# ADC.net
KiCad netlist of a schematic drawn in Altium Designer
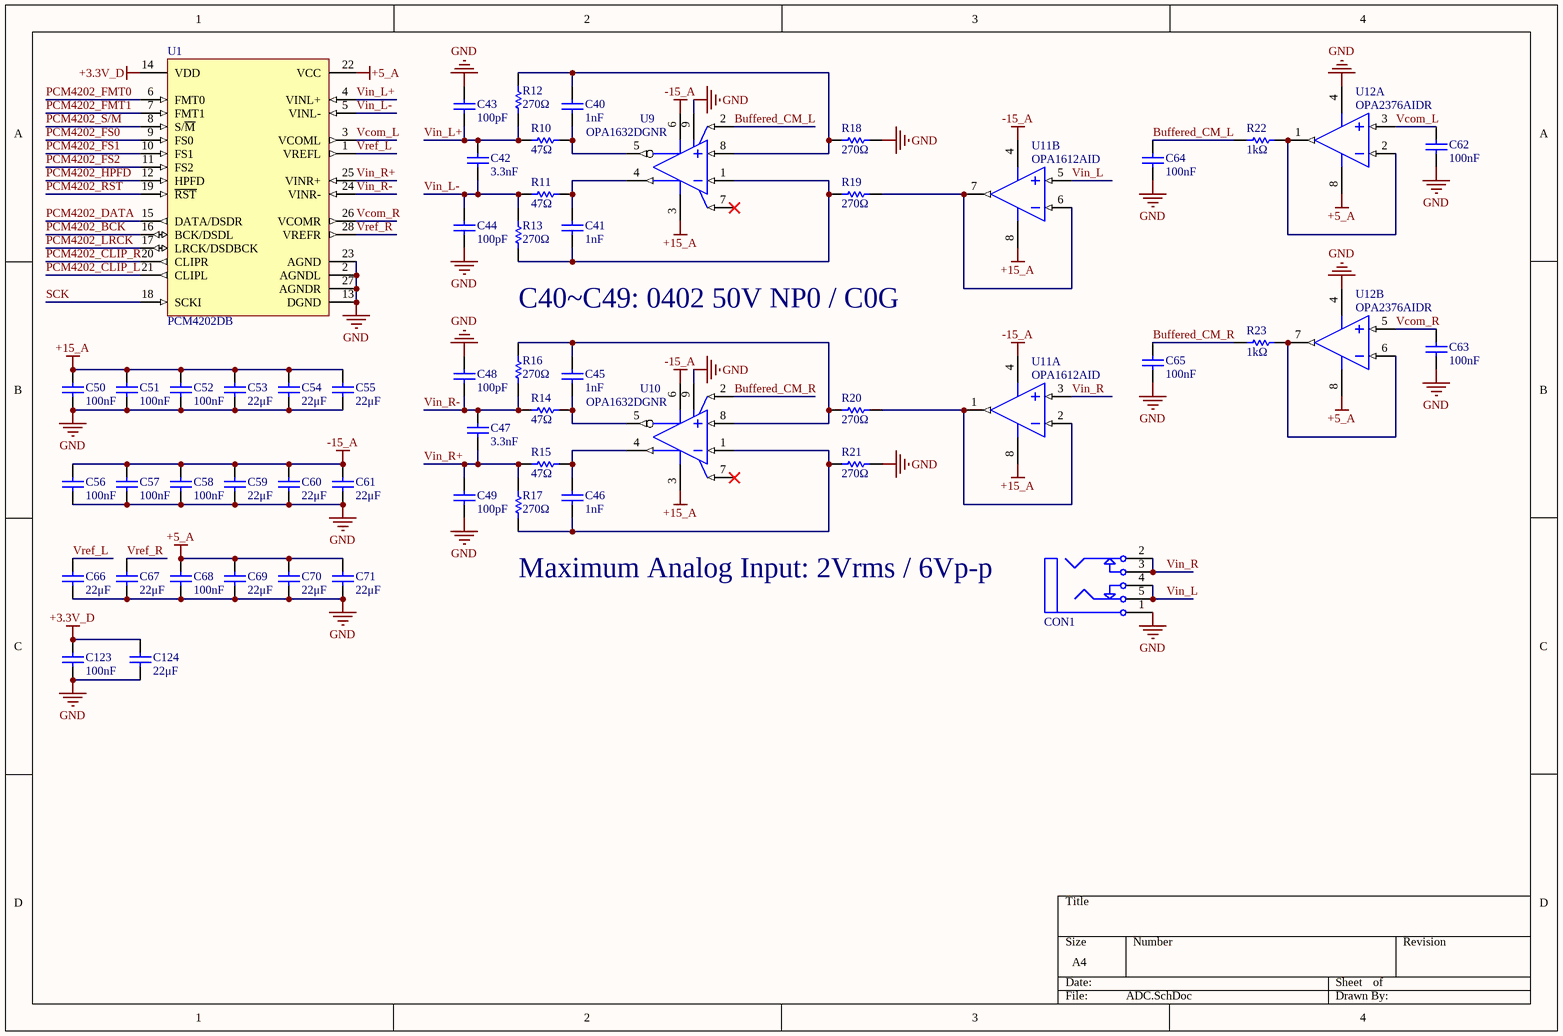
[diagram p0: ADC.SchDoc]

(export (version "E")
  (design (tool "Eeschema 10.0.6"))
  (components
    (comp (ref "C40")
      (value "1nF")
      (footprint "C 0402_L")
      (description "Capacitor")
      (fields (field (name "PUBLISHER") "Altium Limited"))
      (libsource (lib "Miscellaneous Devices") (part "Cap"))
    )
    (comp (ref "C41")
      (value "1nF")
      (footprint "C 0402_L")
      (description "Capacitor")
      (fields (field (name "PUBLISHER") "Altium Limited"))
      (libsource (lib "Miscellaneous Devices") (part "Cap"))
    )
    (comp (ref "C42")
      (value "3.3nF")
      (footprint "C 0402_L")
      (description "Capacitor")
      (fields (field (name "PUBLISHER") "Altium Limited"))
      (libsource (lib "Miscellaneous Devices") (part "Cap"))
    )
    (comp (ref "C43")
      (value "100pF")
      (footprint "C 0402_L")
      (description "Capacitor")
      (fields (field (name "PUBLISHER") "Altium Limited"))
      (libsource (lib "Miscellaneous Devices") (part "Cap"))
    )
    (comp (ref "C44")
      (value "100pF")
      (footprint "C 0402_L")
      (description "Capacitor")
      (fields (field (name "PUBLISHER") "Altium Limited"))
      (libsource (lib "Miscellaneous Devices") (part "Cap"))
    )
    (comp (ref "C45")
      (value "1nF")
      (footprint "C 0402_L")
      (description "Capacitor")
      (fields (field (name "PUBLISHER") "Altium Limited"))
      (libsource (lib "Miscellaneous Devices") (part "Cap"))
    )
    (comp (ref "C46")
      (value "1nF")
      (footprint "C 0402_L")
      (description "Capacitor")
      (fields (field (name "PUBLISHER") "Altium Limited"))
      (libsource (lib "Miscellaneous Devices") (part "Cap"))
    )
    (comp (ref "C47")
      (value "3.3nF")
      (footprint "C 0402_L")
      (description "Capacitor")
      (fields (field (name "PUBLISHER") "Altium Limited"))
      (libsource (lib "Miscellaneous Devices") (part "Cap"))
    )
    (comp (ref "C48")
      (value "100pF")
      (footprint "C 0402_L")
      (description "Capacitor")
      (fields (field (name "PUBLISHER") "Altium Limited"))
      (libsource (lib "Miscellaneous Devices") (part "Cap"))
    )
    (comp (ref "C49")
      (value "100pF")
      (footprint "C 0402_L")
      (description "Capacitor")
      (fields (field (name "PUBLISHER") "Altium Limited"))
      (libsource (lib "Miscellaneous Devices") (part "Cap"))
    )
    (comp (ref "C50")
      (value "100nF")
      (footprint "C 0402_L")
      (description "Capacitor")
      (fields (field (name "PUBLISHER") "Altium Limited"))
      (libsource (lib "Miscellaneous Devices") (part "Cap"))
    )
    (comp (ref "C51")
      (value "100nF")
      (footprint "C 0402_L")
      (description "Capacitor")
      (fields (field (name "PUBLISHER") "Altium Limited"))
      (libsource (lib "Miscellaneous Devices") (part "Cap"))
    )
    (comp (ref "C52")
      (value "100nF")
      (footprint "C 0402_L")
      (description "Capacitor")
      (fields (field (name "PUBLISHER") "Altium Limited"))
      (libsource (lib "Miscellaneous Devices") (part "Cap"))
    )
    (comp (ref "C53")
      (value "22μF")
      (footprint "0805_C")
      (description "Capacitor")
      (fields (field (name "PUBLISHER") "Altium Limited"))
      (libsource (lib "Miscellaneous Devices") (part "Cap"))
    )
    (comp (ref "C54")
      (value "22μF")
      (footprint "0805_C")
      (description "Capacitor")
      (fields (field (name "PUBLISHER") "Altium Limited"))
      (libsource (lib "Miscellaneous Devices") (part "Cap"))
    )
    (comp (ref "C55")
      (value "22μF")
      (footprint "0805_C")
      (description "Capacitor")
      (fields (field (name "PUBLISHER") "Altium Limited"))
      (libsource (lib "Miscellaneous Devices") (part "Cap"))
    )
    (comp (ref "C56")
      (value "100nF")
      (footprint "C 0402_L")
      (description "Capacitor")
      (fields (field (name "PUBLISHER") "Altium Limited"))
      (libsource (lib "Miscellaneous Devices") (part "Cap"))
    )
    (comp (ref "C57")
      (value "100nF")
      (footprint "C 0402_L")
      (description "Capacitor")
      (fields (field (name "PUBLISHER") "Altium Limited"))
      (libsource (lib "Miscellaneous Devices") (part "Cap"))
    )
    (comp (ref "C58")
      (value "100nF")
      (footprint "C 0402_L")
      (description "Capacitor")
      (fields (field (name "PUBLISHER") "Altium Limited"))
      (libsource (lib "Miscellaneous Devices") (part "Cap"))
    )
    (comp (ref "C59")
      (value "22μF")
      (footprint "0805_C")
      (description "Capacitor")
      (fields (field (name "PUBLISHER") "Altium Limited"))
      (libsource (lib "Miscellaneous Devices") (part "Cap"))
    )
    (comp (ref "C60")
      (value "22μF")
      (footprint "0805_C")
      (description "Capacitor")
      (fields (field (name "PUBLISHER") "Altium Limited"))
      (libsource (lib "Miscellaneous Devices") (part "Cap"))
    )
    (comp (ref "C61")
      (value "22μF")
      (footprint "0805_C")
      (description "Capacitor")
      (fields (field (name "PUBLISHER") "Altium Limited"))
      (libsource (lib "Miscellaneous Devices") (part "Cap"))
    )
    (comp (ref "C62")
      (value "100nF")
      (footprint "C 0402_L")
      (description "Capacitor")
      (fields (field (name "PUBLISHER") "Altium Limited"))
      (libsource (lib "Miscellaneous Devices") (part "Cap"))
    )
    (comp (ref "C63")
      (value "100nF")
      (footprint "C 0402_L")
      (description "Capacitor")
      (fields (field (name "PUBLISHER") "Altium Limited"))
      (libsource (lib "Miscellaneous Devices") (part "Cap"))
    )
    (comp (ref "C64")
      (value "100nF")
      (footprint "C 0402_L")
      (description "Capacitor")
      (fields (field (name "PUBLISHER") "Altium Limited"))
      (libsource (lib "Miscellaneous Devices") (part "Cap"))
    )
    (comp (ref "C65")
      (value "100nF")
      (footprint "C 0402_L")
      (description "Capacitor")
      (fields (field (name "PUBLISHER") "Altium Limited"))
      (libsource (lib "Miscellaneous Devices") (part "Cap"))
    )
    (comp (ref "C66")
      (value "22μF")
      (footprint "0805_C")
      (description "Capacitor")
      (fields (field (name "PUBLISHER") "Altium Limited"))
      (libsource (lib "Miscellaneous Devices") (part "Cap"))
    )
    (comp (ref "C67")
      (value "22μF")
      (footprint "0805_C")
      (description "Capacitor")
      (fields (field (name "PUBLISHER") "Altium Limited"))
      (libsource (lib "Miscellaneous Devices") (part "Cap"))
    )
    (comp (ref "C68")
      (value "100nF")
      (footprint "C 0402_L")
      (description "Capacitor")
      (fields (field (name "PUBLISHER") "Altium Limited"))
      (libsource (lib "Miscellaneous Devices") (part "Cap"))
    )
    (comp (ref "C69")
      (value "22μF")
      (footprint "0805_C")
      (description "Capacitor")
      (fields (field (name "PUBLISHER") "Altium Limited"))
      (libsource (lib "Miscellaneous Devices") (part "Cap"))
    )
    (comp (ref "C70")
      (value "22μF")
      (footprint "0805_C")
      (description "Capacitor")
      (fields (field (name "PUBLISHER") "Altium Limited"))
      (libsource (lib "Miscellaneous Devices") (part "Cap"))
    )
    (comp (ref "C71")
      (value "22μF")
      (footprint "0805_C")
      (description "Capacitor")
      (fields (field (name "PUBLISHER") "Altium Limited"))
      (libsource (lib "Miscellaneous Devices") (part "Cap"))
    )
    (comp (ref "C123")
      (value "100nF")
      (footprint "C 0402_L")
      (description "Capacitor")
      (fields (field (name "PUBLISHER") "Altium Limited"))
      (libsource (lib "Miscellaneous Devices") (part "Cap"))
    )
    (comp (ref "C124")
      (value "22μF")
      (footprint "0805_C")
      (description "Capacitor")
      (fields (field (name "PUBLISHER") "Altium Limited"))
      (libsource (lib "Miscellaneous Devices") (part "Cap"))
    )
    (comp (ref "CON1")
      (value "3F07_BK")
      (footprint "3F07_PK")
      (description "3.5mm耳机插座")
      (libsource (lib "04 - 接口类-USB接口-网口") (part "3F07"))
    )
    (comp (ref "R10")
      (value "47Ω")
      (footprint "R 0402_L")
      (description "Resistor")
      (fields (field (name "PUBLISHER") "Altium Limited"))
      (libsource (lib "Miscellaneous Devices") (part "Res1"))
    )
    (comp (ref "R11")
      (value "47Ω")
      (footprint "R 0402_L")
      (description "Resistor")
      (fields (field (name "PUBLISHER") "Altium Limited"))
      (libsource (lib "Miscellaneous Devices") (part "Res1"))
    )
    (comp (ref "R12")
      (value "270Ω")
      (footprint "R 0402_L")
      (description "Resistor")
      (fields (field (name "PUBLISHER") "Altium Limited"))
      (libsource (lib "Miscellaneous Devices") (part "Res1"))
    )
    (comp (ref "R13")
      (value "270Ω")
      (footprint "R 0402_L")
      (description "Resistor")
      (fields (field (name "PUBLISHER") "Altium Limited"))
      (libsource (lib "Miscellaneous Devices") (part "Res1"))
    )
    (comp (ref "R14")
      (value "47Ω")
      (footprint "R 0402_L")
      (description "Resistor")
      (fields (field (name "PUBLISHER") "Altium Limited"))
      (libsource (lib "Miscellaneous Devices") (part "Res1"))
    )
    (comp (ref "R15")
      (value "47Ω")
      (footprint "R 0402_L")
      (description "Resistor")
      (fields (field (name "PUBLISHER") "Altium Limited"))
      (libsource (lib "Miscellaneous Devices") (part "Res1"))
    )
    (comp (ref "R16")
      (value "270Ω")
      (footprint "R 0402_L")
      (description "Resistor")
      (fields (field (name "PUBLISHER") "Altium Limited"))
      (libsource (lib "Miscellaneous Devices") (part "Res1"))
    )
    (comp (ref "R17")
      (value "270Ω")
      (footprint "R 0402_L")
      (description "Resistor")
      (fields (field (name "PUBLISHER") "Altium Limited"))
      (libsource (lib "Miscellaneous Devices") (part "Res1"))
    )
    (comp (ref "R18")
      (value "270Ω")
      (footprint "R 0402_L")
      (description "Resistor")
      (fields (field (name "PUBLISHER") "Altium Limited"))
      (libsource (lib "Miscellaneous Devices") (part "Res1"))
    )
    (comp (ref "R19")
      (value "270Ω")
      (footprint "R 0402_L")
      (description "Resistor")
      (fields (field (name "PUBLISHER") "Altium Limited"))
      (libsource (lib "Miscellaneous Devices") (part "Res1"))
    )
    (comp (ref "R20")
      (value "270Ω")
      (footprint "R 0402_L")
      (description "Resistor")
      (fields (field (name "PUBLISHER") "Altium Limited"))
      (libsource (lib "Miscellaneous Devices") (part "Res1"))
    )
    (comp (ref "R21")
      (value "270Ω")
      (footprint "R 0402_L")
      (description "Resistor")
      (fields (field (name "PUBLISHER") "Altium Limited"))
      (libsource (lib "Miscellaneous Devices") (part "Res1"))
    )
    (comp (ref "R22")
      (value "1kΩ")
      (footprint "R 0402_L")
      (description "Resistor")
      (fields (field (name "PUBLISHER") "Altium Limited"))
      (libsource (lib "Miscellaneous Devices") (part "Res1"))
    )
    (comp (ref "R23")
      (value "1kΩ")
      (footprint "R 0402_L")
      (description "Resistor")
      (fields (field (name "PUBLISHER") "Altium Limited"))
      (libsource (lib "Miscellaneous Devices") (part "Res1"))
    )
    (comp (ref "U1")
      (value "PCM4202DB")
      (footprint "SOP65P780X200-28N")
      (libsource (lib "PCM4202") (part "PCM4202DB"))
    )
    (comp (ref "U9")
      (value "OPA1632DGNR")
      (footprint "DGN0008D_L")
      (fields (field (name "MANUFACTURER") "Texas Instruments"))
      (libsource (lib "OPA1632") (part "CMP-0808-00043-2"))
    )
    (comp (ref "U10")
      (value "OPA1632DGNR")
      (footprint "DGN0008D_L")
      (fields (field (name "MANUFACTURER") "Texas Instruments"))
      (libsource (lib "OPA1632") (part "CMP-0808-00043-2"))
    )
    (comp (ref "U11")
      (value "OPA1612AID")
      (footprint "D0008A_L")
      (fields (field (name "MANUFACTURER") "Texas Instruments"))
      (libsource (lib "OPA1612") (part "CMP-0808-00013-2"))
    )
    (comp (ref "U12")
      (value "OPA2376AIDR")
      (footprint "D0008A_L")
      (fields (field (name "MANUFACTURER") "Texas Instruments"))
      (libsource (lib "OPA2376") (part "CMP-0272-00809-3"))
    )
  )
  (nets
    (net (code "1") (name "+3.3V_D") (class "Default")
      (node (ref "C123") (pin "1") (pinfunction "1_1") (pintype "passive"))
      (node (ref "C124") (pin "1") (pinfunction "1_1") (pintype "passive"))
      (node (ref "U1") (pin "14") (pinfunction "VDD_14") (pintype "power_in"))
    )
    (net (code "2") (name "+5_A") (class "Default")
      (node (ref "C68") (pin "1") (pinfunction "1_1") (pintype "passive"))
      (node (ref "C69") (pin "1") (pinfunction "1_1") (pintype "passive"))
      (node (ref "C70") (pin "1") (pinfunction "1_1") (pintype "passive"))
      (node (ref "C71") (pin "1") (pinfunction "1_1") (pintype "passive"))
      (node (ref "U1") (pin "22") (pinfunction "VCC_22") (pintype "power_in"))
      (node (ref "U12") (pin "8") (pinfunction "V+_8") (pintype "power_in"))
    )
    (net (code "3") (name "+15_A") (class "Default")
      (node (ref "C50") (pin "1") (pinfunction "1_1") (pintype "passive"))
      (node (ref "C51") (pin "1") (pinfunction "1_1") (pintype "passive"))
      (node (ref "C52") (pin "1") (pinfunction "1_1") (pintype "passive"))
      (node (ref "C53") (pin "1") (pinfunction "1_1") (pintype "passive"))
      (node (ref "C54") (pin "1") (pinfunction "1_1") (pintype "passive"))
      (node (ref "C55") (pin "1") (pinfunction "1_1") (pintype "passive"))
      (node (ref "U10") (pin "3") (pinfunction "V+_3") (pintype "power_in"))
      (node (ref "U11") (pin "8") (pinfunction "V+_8") (pintype "power_in"))
      (node (ref "U9") (pin "3") (pinfunction "V+_3") (pintype "power_in"))
    )
    (net (code "4") (name "-15_A") (class "Default")
      (node (ref "C56") (pin "1") (pinfunction "1_1") (pintype "passive"))
      (node (ref "C57") (pin "1") (pinfunction "1_1") (pintype "passive"))
      (node (ref "C58") (pin "1") (pinfunction "1_1") (pintype "passive"))
      (node (ref "C59") (pin "1") (pinfunction "1_1") (pintype "passive"))
      (node (ref "C60") (pin "1") (pinfunction "1_1") (pintype "passive"))
      (node (ref "C61") (pin "1") (pinfunction "1_1") (pintype "passive"))
      (node (ref "U10") (pin "6") (pinfunction "V-_6") (pintype "power_in"))
      (node (ref "U11") (pin "4") (pinfunction "V-_4") (pintype "power_in"))
      (node (ref "U9") (pin "6") (pinfunction "V-_6") (pintype "power_in"))
    )
    (net (code "5") (name "/Buffered_CM_L") (class "Default")
      (node (ref "C64") (pin "1") (pinfunction "1_1") (pintype "passive"))
      (node (ref "R22") (pin "1") (pinfunction "1_1") (pintype "passive"))
      (node (ref "U9") (pin "2") (pinfunction "VOCM_2") (pintype "input"))
    )
    (net (code "6") (name "/Buffered_CM_R") (class "Default")
      (node (ref "C65") (pin "1") (pinfunction "1_1") (pintype "passive"))
      (node (ref "R23") (pin "1") (pinfunction "1_1") (pintype "passive"))
      (node (ref "U10") (pin "2") (pinfunction "VOCM_2") (pintype "input"))
    )
    (net (code "7") (name "/PCM4202_BCK") (class "Default")
      (node (ref "U1") (pin "16") (pinfunction "BCK/DSDL_16") (pintype "bidirectional"))
    )
    (net (code "8") (name "/PCM4202_CLIP_L") (class "Default")
      (node (ref "U1") (pin "21") (pinfunction "CLIPL_21") (pintype "output"))
    )
    (net (code "9") (name "/PCM4202_CLIP_R") (class "Default")
      (node (ref "U1") (pin "20") (pinfunction "CLIPR_20") (pintype "output"))
    )
    (net (code "10") (name "/PCM4202_DATA") (class "Default")
      (node (ref "U1") (pin "15") (pinfunction "DATA/DSDR_15") (pintype "output"))
    )
    (net (code "11") (name "/PCM4202_FMT0") (class "Default")
      (node (ref "U1") (pin "6") (pinfunction "FMT0_6") (pintype "input"))
    )
    (net (code "12") (name "/PCM4202_FMT1") (class "Default")
      (node (ref "U1") (pin "7") (pinfunction "FMT1_7") (pintype "input"))
    )
    (net (code "13") (name "/PCM4202_FS0") (class "Default")
      (node (ref "U1") (pin "9") (pinfunction "FS0_9") (pintype "input"))
    )
    (net (code "14") (name "/PCM4202_FS1") (class "Default")
      (node (ref "U1") (pin "10") (pinfunction "FS1_10") (pintype "input"))
    )
    (net (code "15") (name "/PCM4202_FS2") (class "Default")
      (node (ref "U1") (pin "11") (pinfunction "FS2_11") (pintype "input"))
    )
    (net (code "16") (name "/PCM4202_HPFD") (class "Default")
      (node (ref "U1") (pin "12") (pinfunction "HPFD_12") (pintype "input"))
    )
    (net (code "17") (name "/PCM4202_LRCK") (class "Default")
      (node (ref "U1") (pin "17") (pinfunction "LRCK/DSDBCK_17") (pintype "bidirectional"))
    )
    (net (code "18") (name "/PCM4202_S{slash}~{M}") (class "Default")
      (node (ref "U1") (pin "8") (pinfunction "S/~{M}_8") (pintype "input"))
    )
    (net (code "19") (name "/PCM4202_~{RST}") (class "Default")
      (node (ref "U1") (pin "19") (pinfunction "~{RST}_19") (pintype "input"))
    )
    (net (code "20") (name "/SCK") (class "Default")
      (node (ref "U1") (pin "18") (pinfunction "SCKI_18") (pintype "input"))
    )
    (net (code "21") (name "/Vcom_L") (class "Default")
      (node (ref "C62") (pin "1") (pinfunction "1_1") (pintype "passive"))
      (node (ref "U1") (pin "3") (pinfunction "VCOML_3") (pintype "output"))
      (node (ref "U12") (pin "3") (pinfunction "IN_A+_3") (pintype "input"))
    )
    (net (code "22") (name "/Vcom_R") (class "Default")
      (node (ref "C63") (pin "1") (pinfunction "1_1") (pintype "passive"))
      (node (ref "U1") (pin "26") (pinfunction "VCOMR_26") (pintype "output"))
      (node (ref "U12") (pin "5") (pinfunction "IN_B+_5") (pintype "input"))
    )
    (net (code "23") (name "/Vin_L") (class "Default")
      (node (ref "CON1") (pin "4") (pinfunction "4_4") (pintype "passive"))
      (node (ref "CON1") (pin "5") (pinfunction "5_5") (pintype "passive"))
      (node (ref "U11") (pin "5") (pinfunction "IN_B+_5") (pintype "input"))
    )
    (net (code "24") (name "/Vin_L+") (class "Default")
      (node (ref "C42") (pin "1") (pinfunction "1_1") (pintype "passive"))
      (node (ref "C43") (pin "2") (pinfunction "2_2") (pintype "passive"))
      (node (ref "R10") (pin "2") (pinfunction "2_2") (pintype "passive"))
      (node (ref "R12") (pin "2") (pinfunction "2_2") (pintype "passive"))
      (node (ref "U1") (pin "4") (pinfunction "VINL+_4") (pintype "input"))
    )
    (net (code "25") (name "/Vin_L-") (class "Default")
      (node (ref "C42") (pin "2") (pinfunction "2_2") (pintype "passive"))
      (node (ref "C44") (pin "1") (pinfunction "1_1") (pintype "passive"))
      (node (ref "R11") (pin "2") (pinfunction "2_2") (pintype "passive"))
      (node (ref "R13") (pin "1") (pinfunction "1_1") (pintype "passive"))
      (node (ref "U1") (pin "5") (pinfunction "VINL-_5") (pintype "input"))
    )
    (net (code "26") (name "/Vin_R") (class "Default")
      (node (ref "CON1") (pin "2") (pinfunction "2_2") (pintype "passive"))
      (node (ref "CON1") (pin "3") (pinfunction "3_3") (pintype "passive"))
      (node (ref "U11") (pin "3") (pinfunction "IN_A+_3") (pintype "input"))
    )
    (net (code "27") (name "/Vin_R+") (class "Default")
      (node (ref "C47") (pin "2") (pinfunction "2_2") (pintype "passive"))
      (node (ref "C49") (pin "1") (pinfunction "1_1") (pintype "passive"))
      (node (ref "R15") (pin "2") (pinfunction "2_2") (pintype "passive"))
      (node (ref "R17") (pin "1") (pinfunction "1_1") (pintype "passive"))
      (node (ref "U1") (pin "25") (pinfunction "VINR+_25") (pintype "input"))
    )
    (net (code "28") (name "/Vin_R-") (class "Default")
      (node (ref "C47") (pin "1") (pinfunction "1_1") (pintype "passive"))
      (node (ref "C48") (pin "2") (pinfunction "2_2") (pintype "passive"))
      (node (ref "R14") (pin "2") (pinfunction "2_2") (pintype "passive"))
      (node (ref "R16") (pin "2") (pinfunction "2_2") (pintype "passive"))
      (node (ref "U1") (pin "24") (pinfunction "VINR-_24") (pintype "input"))
    )
    (net (code "29") (name "/Vref_L") (class "Default")
      (node (ref "C66") (pin "1") (pinfunction "1_1") (pintype "passive"))
      (node (ref "U1") (pin "1") (pinfunction "VREFL_1") (pintype "output"))
    )
    (net (code "30") (name "/Vref_R") (class "Default")
      (node (ref "C67") (pin "1") (pinfunction "1_1") (pintype "passive"))
      (node (ref "U1") (pin "28") (pinfunction "VREFR_28") (pintype "output"))
    )
    (net (code "31") (name "GND") (class "Default")
      (node (ref "C123") (pin "2") (pinfunction "2_2") (pintype "passive"))
      (node (ref "C124") (pin "2") (pinfunction "2_2") (pintype "passive"))
      (node (ref "C43") (pin "1") (pinfunction "1_1") (pintype "passive"))
      (node (ref "C44") (pin "2") (pinfunction "2_2") (pintype "passive"))
      (node (ref "C48") (pin "1") (pinfunction "1_1") (pintype "passive"))
      (node (ref "C49") (pin "2") (pinfunction "2_2") (pintype "passive"))
      (node (ref "C50") (pin "2") (pinfunction "2_2") (pintype "passive"))
      (node (ref "C51") (pin "2") (pinfunction "2_2") (pintype "passive"))
      (node (ref "C52") (pin "2") (pinfunction "2_2") (pintype "passive"))
      (node (ref "C53") (pin "2") (pinfunction "2_2") (pintype "passive"))
      (node (ref "C54") (pin "2") (pinfunction "2_2") (pintype "passive"))
      (node (ref "C55") (pin "2") (pinfunction "2_2") (pintype "passive"))
      (node (ref "C56") (pin "2") (pinfunction "2_2") (pintype "passive"))
      (node (ref "C57") (pin "2") (pinfunction "2_2") (pintype "passive"))
      (node (ref "C58") (pin "2") (pinfunction "2_2") (pintype "passive"))
      (node (ref "C59") (pin "2") (pinfunction "2_2") (pintype "passive"))
      (node (ref "C60") (pin "2") (pinfunction "2_2") (pintype "passive"))
      (node (ref "C61") (pin "2") (pinfunction "2_2") (pintype "passive"))
      (node (ref "C62") (pin "2") (pinfunction "2_2") (pintype "passive"))
      (node (ref "C63") (pin "2") (pinfunction "2_2") (pintype "passive"))
      (node (ref "C64") (pin "2") (pinfunction "2_2") (pintype "passive"))
      (node (ref "C65") (pin "2") (pinfunction "2_2") (pintype "passive"))
      (node (ref "C66") (pin "2") (pinfunction "2_2") (pintype "passive"))
      (node (ref "C67") (pin "2") (pinfunction "2_2") (pintype "passive"))
      (node (ref "C68") (pin "2") (pinfunction "2_2") (pintype "passive"))
      (node (ref "C69") (pin "2") (pinfunction "2_2") (pintype "passive"))
      (node (ref "C70") (pin "2") (pinfunction "2_2") (pintype "passive"))
      (node (ref "C71") (pin "2") (pinfunction "2_2") (pintype "passive"))
      (node (ref "CON1") (pin "1") (pinfunction "1_1") (pintype "passive"))
      (node (ref "R18") (pin "2") (pinfunction "2_2") (pintype "passive"))
      (node (ref "R21") (pin "2") (pinfunction "2_2") (pintype "passive"))
      (node (ref "U1") (pin "13") (pinfunction "DGND_13") (pintype "power_in"))
      (node (ref "U1") (pin "2") (pinfunction "AGNDL_2") (pintype "power_in"))
      (node (ref "U1") (pin "23") (pinfunction "AGND_23") (pintype "power_in"))
      (node (ref "U1") (pin "27") (pinfunction "AGNDR_27") (pintype "power_in"))
      (node (ref "U10") (pin "9") (pinfunction "EP_9") (pintype "passive"))
      (node (ref "U12") (pin "4") (pinfunction "V-_4") (pintype "power_in"))
      (node (ref "U9") (pin "9") (pinfunction "EP_9") (pintype "passive"))
    )
    (net (code "32") (name "Net-(U9-VIN+)") (class "Default")
      (node (ref "C40") (pin "2") (pinfunction "2_2") (pintype "passive"))
      (node (ref "R12") (pin "1") (pinfunction "1_1") (pintype "passive"))
      (node (ref "R18") (pin "1") (pinfunction "1_1") (pintype "passive"))
      (node (ref "U9") (pin "8") (pinfunction "VIN+_8") (pintype "input"))
    )
    (net (code "33") (name "Net-(U9-VIN-)") (class "Default")
      (node (ref "C41") (pin "2") (pinfunction "2_2") (pintype "passive"))
      (node (ref "R13") (pin "2") (pinfunction "2_2") (pintype "passive"))
      (node (ref "R19") (pin "1") (pinfunction "1_1") (pintype "passive"))
      (node (ref "U9") (pin "1") (pinfunction "VIN-_1") (pintype "input"))
    )
    (net (code "34") (name "Net-(U9-VOUT+)") (class "Default")
      (node (ref "C41") (pin "1") (pinfunction "1_1") (pintype "passive"))
      (node (ref "R11") (pin "1") (pinfunction "1_1") (pintype "passive"))
      (node (ref "U9") (pin "4") (pinfunction "VOUT+_4") (pintype "output"))
    )
    (net (code "35") (name "Net-(U9-VOUT-)") (class "Default")
      (node (ref "C40") (pin "1") (pinfunction "1_1") (pintype "passive"))
      (node (ref "R10") (pin "1") (pinfunction "1_1") (pintype "passive"))
      (node (ref "U9") (pin "5") (pinfunction "VOUT-_5") (pintype "output"))
    )
    (net (code "36") (name "Net-(U10-VIN+)") (class "Default")
      (node (ref "C45") (pin "2") (pinfunction "2_2") (pintype "passive"))
      (node (ref "R16") (pin "1") (pinfunction "1_1") (pintype "passive"))
      (node (ref "R20") (pin "1") (pinfunction "1_1") (pintype "passive"))
      (node (ref "U10") (pin "8") (pinfunction "VIN+_8") (pintype "input"))
    )
    (net (code "37") (name "Net-(U10-VIN-)") (class "Default")
      (node (ref "C46") (pin "2") (pinfunction "2_2") (pintype "passive"))
      (node (ref "R17") (pin "2") (pinfunction "2_2") (pintype "passive"))
      (node (ref "R21") (pin "1") (pinfunction "1_1") (pintype "passive"))
      (node (ref "U10") (pin "1") (pinfunction "VIN-_1") (pintype "input"))
    )
    (net (code "38") (name "Net-(U10-VOUT+)") (class "Default")
      (node (ref "C46") (pin "1") (pinfunction "1_1") (pintype "passive"))
      (node (ref "R15") (pin "1") (pinfunction "1_1") (pintype "passive"))
      (node (ref "U10") (pin "4") (pinfunction "VOUT+_4") (pintype "output"))
    )
    (net (code "39") (name "Net-(U10-VOUT-)") (class "Default")
      (node (ref "C45") (pin "1") (pinfunction "1_1") (pintype "passive"))
      (node (ref "R14") (pin "1") (pinfunction "1_1") (pintype "passive"))
      (node (ref "U10") (pin "5") (pinfunction "VOUT-_5") (pintype "output"))
    )
    (net (code "40") (name "Net-(U11A-IN_A-)") (class "Default")
      (node (ref "R20") (pin "2") (pinfunction "2_2") (pintype "passive"))
      (node (ref "U11") (pin "1") (pinfunction "OUT_A_1") (pintype "output"))
      (node (ref "U11") (pin "2") (pinfunction "IN_A-_2") (pintype "input"))
    )
    (net (code "41") (name "Net-(U11B-IN_B-)") (class "Default")
      (node (ref "R19") (pin "2") (pinfunction "2_2") (pintype "passive"))
      (node (ref "U11") (pin "6") (pinfunction "IN_B-_6") (pintype "input"))
      (node (ref "U11") (pin "7") (pinfunction "OUT_B_7") (pintype "output"))
    )
    (net (code "42") (name "Net-(U12A-IN_A-)") (class "Default")
      (node (ref "R22") (pin "2") (pinfunction "2_2") (pintype "passive"))
      (node (ref "U12") (pin "1") (pinfunction "OUT_A_1") (pintype "output"))
      (node (ref "U12") (pin "2") (pinfunction "IN_A-_2") (pintype "input"))
    )
    (net (code "43") (name "Net-(U12B-IN_B-)") (class "Default")
      (node (ref "R23") (pin "2") (pinfunction "2_2") (pintype "passive"))
      (node (ref "U12") (pin "6") (pinfunction "IN_B-_6") (pintype "input"))
      (node (ref "U12") (pin "7") (pinfunction "OUT_B_7") (pintype "output"))
    )
    (net (code "44") (name "unconnected-(U9-ENABLE-Pad7)") (class "Default")
      (node (ref "U9") (pin "7") (pinfunction "ENABLE_7") (pintype "input+no_connect"))
    )
    (net (code "45") (name "unconnected-(U10-ENABLE-Pad7)") (class "Default")
      (node (ref "U10") (pin "7") (pinfunction "ENABLE_7") (pintype "input+no_connect"))
    )
  )
)
